# design.net
KiCad netlist of a schematic drawn in Altium Designer
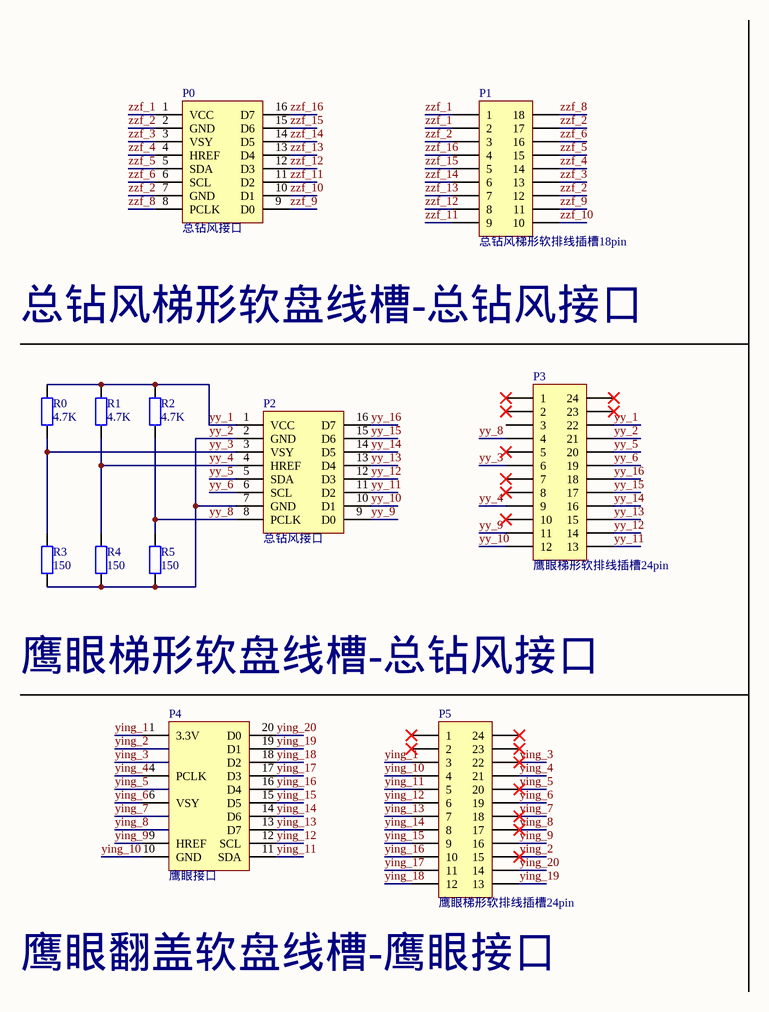
[diagram p0: 摄像头转接板原理图.SchDoc]

(export (version "E")
  (design (tool "Eeschema 10.0.6"))
  (components
    (comp (ref "P0")
      (value "总钻风接口")
      (footprint "总钻风MT9V032")
      (fields (field (name "PUBLISHER") "Altium Limited"))
      (libsource (lib "SCH普通元件库") (part "总钻风MT9V032"))
    )
    (comp (ref "P1")
      (value "总钻风梯形软排线插槽18pin")
      (footprint "总钻风软排线梯形插槽-18pin")
      (description "软排线插槽, 18-Pin")
      (fields (field (name "PUBLISHER") "Altium Limited"))
      (libsource (lib "SCH普通元件库") (part "梯形软排线插槽18pin"))
    )
    (comp (ref "P2")
      (value "总钻风接口")
      (footprint "总钻风MT9V032")
      (fields (field (name "PUBLISHER") "Altium Limited"))
      (libsource (lib "SCH普通元件库") (part "总钻风MT9V032"))
    )
    (comp (ref "P3")
      (value "鹰眼梯形软排线插槽24pin")
      (footprint "鹰眼软排线梯形插槽-24pin")
      (description "软排线插槽, 24-Pin")
      (fields (field (name "PUBLISHER") "Altium Limited"))
      (libsource (lib "SCH普通元件库") (part "梯形软排线插槽24pin"))
    )
    (comp (ref "P4")
      (value "鹰眼接口")
      (footprint "山外OV7725插座")
      (fields (field (name "PUBLISHER") "Altium Limited"))
      (libsource (lib "SCH普通元件库") (part "山外OV7725"))
    )
    (comp (ref "P5")
      (value "鹰眼梯形软排线插槽24pin")
      (footprint "鹰眼软排线梯形插槽-24pin")
      (description "软排线插槽, 24-Pin")
      (fields (field (name "PUBLISHER") "Altium Limited"))
      (libsource (lib "SCH普通元件库") (part "鹰眼梯形软排线插槽24pin"))
    )
    (comp (ref "R0") (value "4.7K") (footprint "0805") (libsource (lib "") (part "R-0805_1")))
    (comp (ref "R1") (value "4.7K") (footprint "0805") (libsource (lib "SCH小元件库") (part "R-0805")))
    (comp (ref "R2") (value "4.7K") (footprint "0805") (libsource (lib "SCH小元件库") (part "R-0805")))
    (comp (ref "R3") (value "150") (footprint "0805") (libsource (lib "SCH小元件库") (part "R-0805")))
    (comp (ref "R4") (value "150") (footprint "0805") (libsource (lib "SCH小元件库") (part "R-0805")))
    (comp (ref "R5") (value "150") (footprint "0805") (libsource (lib "SCH小元件库") (part "R-0805")))
  )
  (nets
    (net (code "1") (name "/ying_1") (class "Default")
      (node (ref "P4") (pin "1") (pinfunction "3.3V_1") (pintype "passive"))
      (node (ref "P5") (pin "3") (pinfunction "3_3") (pintype "passive"))
    )
    (net (code "2") (name "/ying_2") (class "Default")
      (node (ref "P5") (pin "15") (pinfunction "15_15") (pintype "passive"))
    )
    (net (code "3") (name "/ying_3") (class "Default")
      (node (ref "P5") (pin "22") (pinfunction "22_22") (pintype "passive"))
    )
    (net (code "4") (name "/ying_4") (class "Default")
      (node (ref "P4") (pin "4") (pinfunction "PCLK_4") (pintype "passive"))
      (node (ref "P5") (pin "21") (pinfunction "21_21") (pintype "passive"))
    )
    (net (code "5") (name "/ying_5") (class "Default")
      (node (ref "P5") (pin "20") (pinfunction "20_20") (pintype "passive"))
    )
    (net (code "6") (name "/ying_6") (class "Default")
      (node (ref "P4") (pin "6") (pinfunction "VSY_6") (pintype "passive"))
      (node (ref "P5") (pin "19") (pinfunction "19_19") (pintype "passive"))
    )
    (net (code "7") (name "/ying_7") (class "Default")
      (node (ref "P5") (pin "18") (pinfunction "18_18") (pintype "passive"))
    )
    (net (code "8") (name "/ying_8") (class "Default")
      (node (ref "P5") (pin "17") (pinfunction "17_17") (pintype "passive"))
    )
    (net (code "9") (name "/ying_9") (class "Default")
      (node (ref "P4") (pin "9") (pinfunction "HREF_9") (pintype "passive"))
      (node (ref "P5") (pin "16") (pinfunction "16_16") (pintype "passive"))
    )
    (net (code "10") (name "/ying_10") (class "Default")
      (node (ref "P4") (pin "10") (pinfunction "GND_10") (pintype "passive"))
      (node (ref "P5") (pin "4") (pinfunction "4_4") (pintype "passive"))
    )
    (net (code "11") (name "/ying_11") (class "Default")
      (node (ref "P4") (pin "11") (pinfunction "SDA_11") (pintype "passive"))
      (node (ref "P5") (pin "5") (pinfunction "5_5") (pintype "passive"))
    )
    (net (code "12") (name "/ying_12") (class "Default")
      (node (ref "P4") (pin "12") (pinfunction "SCL_12") (pintype "passive"))
      (node (ref "P5") (pin "6") (pinfunction "6_6") (pintype "passive"))
    )
    (net (code "13") (name "/ying_13") (class "Default")
      (node (ref "P4") (pin "13") (pinfunction "D7_13") (pintype "passive"))
      (node (ref "P5") (pin "7") (pinfunction "7_7") (pintype "passive"))
    )
    (net (code "14") (name "/ying_14") (class "Default")
      (node (ref "P4") (pin "14") (pinfunction "D6_14") (pintype "passive"))
      (node (ref "P5") (pin "8") (pinfunction "8_8") (pintype "passive"))
    )
    (net (code "15") (name "/ying_15") (class "Default")
      (node (ref "P4") (pin "15") (pinfunction "D5_15") (pintype "passive"))
      (node (ref "P5") (pin "9") (pinfunction "9_9") (pintype "passive"))
    )
    (net (code "16") (name "/ying_16") (class "Default")
      (node (ref "P4") (pin "16") (pinfunction "D4_16") (pintype "passive"))
      (node (ref "P5") (pin "10") (pinfunction "10_10") (pintype "passive"))
    )
    (net (code "17") (name "/ying_17") (class "Default")
      (node (ref "P4") (pin "17") (pinfunction "D3_17") (pintype "passive"))
      (node (ref "P5") (pin "11") (pinfunction "11_11") (pintype "passive"))
    )
    (net (code "18") (name "/ying_18") (class "Default")
      (node (ref "P4") (pin "18") (pinfunction "D2_18") (pintype "passive"))
      (node (ref "P5") (pin "12") (pinfunction "12_12") (pintype "passive"))
    )
    (net (code "19") (name "/ying_19") (class "Default")
      (node (ref "P4") (pin "19") (pinfunction "D1_19") (pintype "passive"))
      (node (ref "P5") (pin "13") (pinfunction "13_13") (pintype "passive"))
    )
    (net (code "20") (name "/ying_20") (class "Default")
      (node (ref "P4") (pin "20") (pinfunction "D0_20") (pintype "passive"))
      (node (ref "P5") (pin "14") (pinfunction "14_14") (pintype "passive"))
    )
    (net (code "21") (name "/yy_1") (class "Default")
      (node (ref "P2") (pin "1") (pinfunction "VCC_1") (pintype "passive"))
      (node (ref "P3") (pin "22") (pinfunction "22_22") (pintype "passive"))
      (node (ref "R0") (pin "1") (pinfunction "1_1") (pintype "passive"))
      (node (ref "R1") (pin "2") (pinfunction "2_2") (pintype "passive"))
      (node (ref "R2") (pin "2") (pinfunction "2_2") (pintype "passive"))
    )
    (net (code "22") (name "/yy_2") (class "Default")
      (node (ref "P2") (pin "2") (pinfunction "GND_2") (pintype "passive"))
      (node (ref "P2") (pin "7") (pinfunction "GND_7") (pintype "passive"))
      (node (ref "P3") (pin "21") (pinfunction "21_21") (pintype "passive"))
      (node (ref "R3") (pin "1") (pinfunction "1_1") (pintype "passive"))
      (node (ref "R4") (pin "1") (pinfunction "1_1") (pintype "passive"))
      (node (ref "R5") (pin "1") (pinfunction "1_1") (pintype "passive"))
    )
    (net (code "23") (name "/yy_3") (class "Default")
      (node (ref "P2") (pin "3") (pinfunction "VSY_3") (pintype "passive"))
      (node (ref "P3") (pin "6") (pinfunction "6_6") (pintype "passive"))
      (node (ref "R0") (pin "2") (pinfunction "2_2") (pintype "passive"))
      (node (ref "R3") (pin "2") (pinfunction "2_2") (pintype "passive"))
    )
    (net (code "24") (name "/yy_4") (class "Default")
      (node (ref "P2") (pin "4") (pinfunction "HREF_4") (pintype "passive"))
      (node (ref "P3") (pin "9") (pinfunction "9_9") (pintype "passive"))
      (node (ref "R1") (pin "1") (pinfunction "1_1") (pintype "passive"))
      (node (ref "R4") (pin "2") (pinfunction "2_2") (pintype "passive"))
    )
    (net (code "25") (name "/yy_5") (class "Default")
      (node (ref "P2") (pin "5") (pinfunction "SDA_5") (pintype "passive"))
      (node (ref "P3") (pin "20") (pinfunction "20_20") (pintype "passive"))
    )
    (net (code "26") (name "/yy_6") (class "Default")
      (node (ref "P2") (pin "6") (pinfunction "SCL_6") (pintype "passive"))
      (node (ref "P3") (pin "19") (pinfunction "19_19") (pintype "passive"))
    )
    (net (code "27") (name "/yy_8") (class "Default")
      (node (ref "P2") (pin "8") (pinfunction "PCLK_8") (pintype "passive"))
      (node (ref "P3") (pin "4") (pinfunction "4_4") (pintype "passive"))
      (node (ref "R2") (pin "1") (pinfunction "1_1") (pintype "passive"))
      (node (ref "R5") (pin "2") (pinfunction "2_2") (pintype "passive"))
    )
    (net (code "28") (name "/yy_9") (class "Default")
      (node (ref "P2") (pin "9") (pinfunction "D0_9") (pintype "passive"))
      (node (ref "P3") (pin "11") (pinfunction "11_11") (pintype "passive"))
    )
    (net (code "29") (name "/yy_10") (class "Default")
      (node (ref "P2") (pin "10") (pinfunction "D1_10") (pintype "passive"))
      (node (ref "P3") (pin "12") (pinfunction "12_12") (pintype "passive"))
    )
    (net (code "30") (name "/yy_11") (class "Default")
      (node (ref "P2") (pin "11") (pinfunction "D2_11") (pintype "passive"))
      (node (ref "P3") (pin "13") (pinfunction "13_13") (pintype "passive"))
    )
    (net (code "31") (name "/yy_12") (class "Default")
      (node (ref "P2") (pin "12") (pinfunction "D3_12") (pintype "passive"))
      (node (ref "P3") (pin "14") (pinfunction "14_14") (pintype "passive"))
    )
    (net (code "32") (name "/yy_13") (class "Default")
      (node (ref "P2") (pin "13") (pinfunction "D4_13") (pintype "passive"))
      (node (ref "P3") (pin "15") (pinfunction "15_15") (pintype "passive"))
    )
    (net (code "33") (name "/yy_14") (class "Default")
      (node (ref "P2") (pin "14") (pinfunction "D5_14") (pintype "passive"))
      (node (ref "P3") (pin "16") (pinfunction "16_16") (pintype "passive"))
    )
    (net (code "34") (name "/yy_15") (class "Default")
      (node (ref "P2") (pin "15") (pinfunction "D6_15") (pintype "passive"))
      (node (ref "P3") (pin "17") (pinfunction "17_17") (pintype "passive"))
    )
    (net (code "35") (name "/yy_16") (class "Default")
      (node (ref "P2") (pin "16") (pinfunction "D7_16") (pintype "passive"))
      (node (ref "P3") (pin "18") (pinfunction "18_18") (pintype "passive"))
    )
    (net (code "36") (name "/zzf_1") (class "Default")
      (node (ref "P0") (pin "1") (pinfunction "VCC_1") (pintype "passive"))
      (node (ref "P1") (pin "1") (pinfunction "1_1") (pintype "passive"))
      (node (ref "P1") (pin "2") (pinfunction "2_2") (pintype "passive"))
    )
    (net (code "37") (name "/zzf_2") (class "Default")
      (node (ref "P0") (pin "2") (pinfunction "GND_2") (pintype "passive"))
      (node (ref "P0") (pin "7") (pinfunction "GND_7") (pintype "passive"))
      (node (ref "P1") (pin "12") (pinfunction "12_12") (pintype "passive"))
      (node (ref "P1") (pin "17") (pinfunction "17_17") (pintype "passive"))
      (node (ref "P1") (pin "3") (pinfunction "3_3") (pintype "passive"))
    )
    (net (code "38") (name "/zzf_3") (class "Default")
      (node (ref "P0") (pin "3") (pinfunction "VSY_3") (pintype "passive"))
      (node (ref "P1") (pin "13") (pinfunction "13_13") (pintype "passive"))
    )
    (net (code "39") (name "/zzf_4") (class "Default")
      (node (ref "P0") (pin "4") (pinfunction "HREF_4") (pintype "passive"))
      (node (ref "P1") (pin "14") (pinfunction "14_14") (pintype "passive"))
    )
    (net (code "40") (name "/zzf_5") (class "Default")
      (node (ref "P0") (pin "5") (pinfunction "SDA_5") (pintype "passive"))
      (node (ref "P1") (pin "15") (pinfunction "15_15") (pintype "passive"))
    )
    (net (code "41") (name "/zzf_6") (class "Default")
      (node (ref "P0") (pin "6") (pinfunction "SCL_6") (pintype "passive"))
      (node (ref "P1") (pin "16") (pinfunction "16_16") (pintype "passive"))
    )
    (net (code "42") (name "/zzf_8") (class "Default")
      (node (ref "P0") (pin "8") (pinfunction "PCLK_8") (pintype "passive"))
      (node (ref "P1") (pin "18") (pinfunction "18_18") (pintype "passive"))
    )
    (net (code "43") (name "/zzf_9") (class "Default")
      (node (ref "P0") (pin "9") (pinfunction "D0_9") (pintype "passive"))
      (node (ref "P1") (pin "11") (pinfunction "11_11") (pintype "passive"))
    )
    (net (code "44") (name "/zzf_10") (class "Default")
      (node (ref "P0") (pin "10") (pinfunction "D1_10") (pintype "passive"))
      (node (ref "P1") (pin "10") (pinfunction "10_10") (pintype "passive"))
    )
    (net (code "45") (name "/zzf_11") (class "Default")
      (node (ref "P0") (pin "11") (pinfunction "D2_11") (pintype "passive"))
      (node (ref "P1") (pin "9") (pinfunction "9_9") (pintype "passive"))
    )
    (net (code "46") (name "/zzf_12") (class "Default")
      (node (ref "P0") (pin "12") (pinfunction "D3_12") (pintype "passive"))
      (node (ref "P1") (pin "8") (pinfunction "8_8") (pintype "passive"))
    )
    (net (code "47") (name "/zzf_13") (class "Default")
      (node (ref "P0") (pin "13") (pinfunction "D4_13") (pintype "passive"))
      (node (ref "P1") (pin "7") (pinfunction "7_7") (pintype "passive"))
    )
    (net (code "48") (name "/zzf_14") (class "Default")
      (node (ref "P0") (pin "14") (pinfunction "D5_14") (pintype "passive"))
      (node (ref "P1") (pin "6") (pinfunction "6_6") (pintype "passive"))
    )
    (net (code "49") (name "/zzf_15") (class "Default")
      (node (ref "P0") (pin "15") (pinfunction "D6_15") (pintype "passive"))
      (node (ref "P1") (pin "5") (pinfunction "5_5") (pintype "passive"))
    )
    (net (code "50") (name "/zzf_16") (class "Default")
      (node (ref "P0") (pin "16") (pinfunction "D7_16") (pintype "passive"))
      (node (ref "P1") (pin "4") (pinfunction "4_4") (pintype "passive"))
    )
    (net (code "51") (name "unconnected-(P3-Pad1)") (class "Default")
      (node (ref "P3") (pin "1") (pinfunction "1_1") (pintype "passive+no_connect"))
    )
    (net (code "52") (name "unconnected-(P3-Pad2)") (class "Default")
      (node (ref "P3") (pin "2") (pinfunction "2_2") (pintype "passive+no_connect"))
    )
    (net (code "53") (name "unconnected-(P3-Pad3)") (class "Default")
      (node (ref "P3") (pin "3") (pinfunction "3_3") (pintype "passive"))
    )
    (net (code "54") (name "unconnected-(P3-Pad5)") (class "Default")
      (node (ref "P3") (pin "5") (pinfunction "5_5") (pintype "passive+no_connect"))
    )
    (net (code "55") (name "unconnected-(P3-Pad7)") (class "Default")
      (node (ref "P3") (pin "7") (pinfunction "7_7") (pintype "passive+no_connect"))
    )
    (net (code "56") (name "unconnected-(P3-Pad8)") (class "Default")
      (node (ref "P3") (pin "8") (pinfunction "8_8") (pintype "passive+no_connect"))
    )
    (net (code "57") (name "unconnected-(P3-Pad10)") (class "Default")
      (node (ref "P3") (pin "10") (pinfunction "10_10") (pintype "passive+no_connect"))
    )
    (net (code "58") (name "unconnected-(P3-Pad23)") (class "Default")
      (node (ref "P3") (pin "23") (pinfunction "23_23") (pintype "passive+no_connect"))
    )
    (net (code "59") (name "unconnected-(P3-Pad24)") (class "Default")
      (node (ref "P3") (pin "24") (pinfunction "24_24") (pintype "passive+no_connect"))
    )
    (net (code "60") (name "unconnected-(P5-Pad1)") (class "Default")
      (node (ref "P5") (pin "1") (pinfunction "1_1") (pintype "passive+no_connect"))
    )
    (net (code "61") (name "unconnected-(P5-Pad2)") (class "Default")
      (node (ref "P5") (pin "2") (pinfunction "2_2") (pintype "passive+no_connect"))
    )
    (net (code "62") (name "unconnected-(P5-Pad23)") (class "Default")
      (node (ref "P5") (pin "23") (pinfunction "23_23") (pintype "passive+no_connect"))
    )
    (net (code "63") (name "unconnected-(P5-Pad24)") (class "Default")
      (node (ref "P5") (pin "24") (pinfunction "24_24") (pintype "passive+no_connect"))
    )
  )
)
